# MIDI_CV_atmega_max528_v2_5.net
KiCad netlist of a schematic drawn in EAGLE
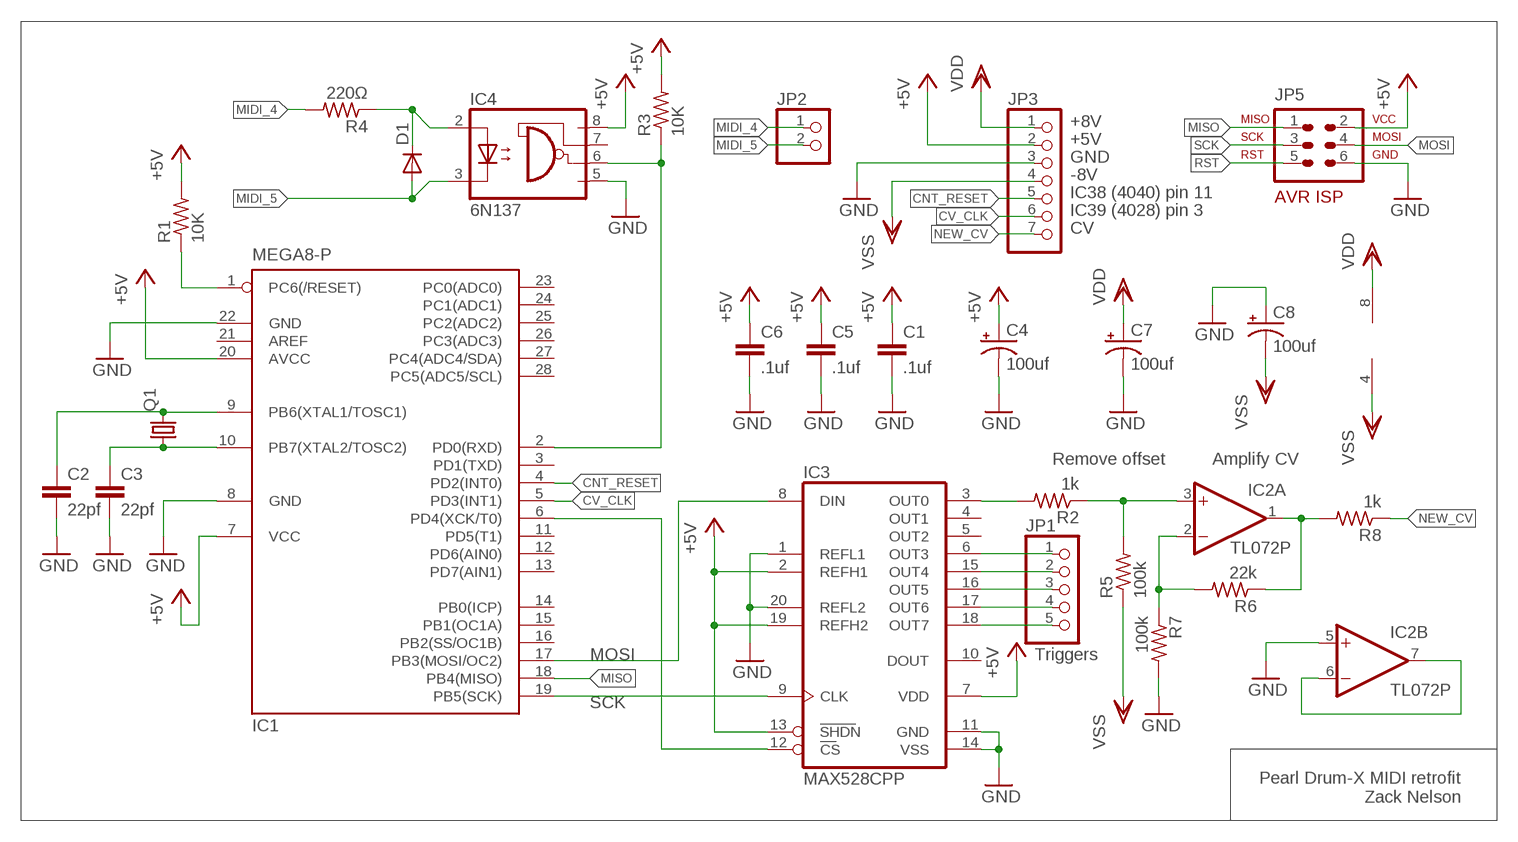
[diagram p0: schematic, sheet 1]

(export (version "E")
  (design (tool "Eeschema 10.0.6"))
  (components
    (comp (ref "C1")
      (value ".1uf")
      (footprint "eagle-import:C025-024X044")
      (libsource (lib "eagle-import") (part "C-EU025-024X044"))
    )
    (comp (ref "C2")
      (value "22pf")
      (footprint "eagle-import:C025-024X044")
      (libsource (lib "eagle-import") (part "C-EU025-024X044"))
    )
    (comp (ref "C3")
      (value "22pf")
      (footprint "eagle-import:C025-024X044")
      (libsource (lib "eagle-import") (part "C-EU025-024X044"))
    )
    (comp (ref "C4")
      (value "100uf")
      (footprint "eagle-import:E1,8-4")
      (libsource (lib "eagle-import") (part "CPOL-USE1.8-4"))
    )
    (comp (ref "C5")
      (value ".1uf")
      (footprint "eagle-import:C025-024X044")
      (libsource (lib "eagle-import") (part "C-EU025-024X044"))
    )
    (comp (ref "C6")
      (value ".1uf")
      (footprint "eagle-import:C025-024X044")
      (libsource (lib "eagle-import") (part "C-EU025-024X044"))
    )
    (comp (ref "C7")
      (value "100uf")
      (footprint "eagle-import:E1,8-4")
      (libsource (lib "eagle-import") (part "CPOL-USE1.8-4"))
    )
    (comp (ref "C8")
      (value "100uf")
      (footprint "eagle-import:E1,8-4")
      (libsource (lib "eagle-import") (part "CPOL-USE1.8-4"))
    )
    (comp (ref "D1")
      (value "DIODE-D-2.5")
      (footprint "eagle-import:D-2.5")
      (libsource (lib "eagle-import") (part "DIODE-D-2.5"))
    )
    (comp (ref "IC1")
      (value "MEGA8-P")
      (footprint "eagle-import:DIL28-3")
      (libsource (lib "eagle-import") (part "MEGA8-P"))
    )
    (comp (ref "IC2")
      (value "TL072P")
      (footprint "eagle-import:DIL08")
      (libsource (lib "eagle-import") (part "TL072P"))
    )
    (comp (ref "IC3")
      (value "MAX528CPP")
      (footprint "eagle-import:DIL20")
      (libsource (lib "eagle-import") (part "MAX528CPP"))
    )
    (comp (ref "IC4")
      (value "6N137")
      (footprint "eagle-import:DIL08")
      (libsource (lib "eagle-import") (part "6N137"))
    )
    (comp (ref "JP1")
      (value "PINHD-1X5")
      (footprint "eagle-import:1X05")
      (libsource (lib "eagle-import") (part "PINHD-1X5"))
    )
    (comp (ref "JP2")
      (value "PINHD-1X2")
      (footprint "eagle-import:1X02")
      (libsource (lib "eagle-import") (part "PINHD-1X2"))
    )
    (comp (ref "JP3")
      (value "PINHD-1X7")
      (footprint "eagle-import:1X07")
      (libsource (lib "eagle-import") (part "PINHD-1X7"))
    )
    (comp (ref "JP5")
      (value "AVR-ISP-6VERT")
      (footprint "eagle-import:AVR-ISP-6")
      (libsource (lib "eagle-import") (part "AVR-ISP-6VERT"))
    )
    (comp (ref "Q1")
      (value "CRYSTALHC18U-V")
      (footprint "eagle-import:HC18U-V")
      (libsource (lib "eagle-import") (part "CRYSTALHC18U-V"))
    )
    (comp (ref "R1")
      (value "10K")
      (footprint "eagle-import:0204V")
      (libsource (lib "eagle-import") (part "R-US_0204/2V"))
    )
    (comp (ref "R2")
      (value "1k")
      (footprint "eagle-import:0204V")
      (libsource (lib "eagle-import") (part "R-US_0204/2V"))
    )
    (comp (ref "R3")
      (value "10K")
      (footprint "eagle-import:0204V")
      (libsource (lib "eagle-import") (part "R-US_0204/2V"))
    )
    (comp (ref "R4")
      (value "220Ω")
      (footprint "eagle-import:0204V")
      (libsource (lib "eagle-import") (part "R-US_0204/2V"))
    )
    (comp (ref "R5")
      (value "100k")
      (footprint "eagle-import:0204V")
      (libsource (lib "eagle-import") (part "R-US_0204/2V"))
    )
    (comp (ref "R6")
      (value "22k")
      (footprint "eagle-import:0204V")
      (libsource (lib "eagle-import") (part "R-US_0204/2V"))
    )
    (comp (ref "R7")
      (value "100k")
      (footprint "eagle-import:0204V")
      (libsource (lib "eagle-import") (part "R-US_0204/2V"))
    )
    (comp (ref "R8")
      (value "1k")
      (footprint "eagle-import:0204V")
      (libsource (lib "eagle-import") (part "R-US_0204/2V"))
    )
  )
  (nets
    (net (code "1") (name "+5V") (class "Default")
      (node (ref "C1") (pin "1") (pinfunction "1_1") (pintype "passive"))
      (node (ref "C4") (pin "+") (pinfunction "+_+") (pintype "passive"))
      (node (ref "C5") (pin "1") (pinfunction "1_1") (pintype "passive"))
      (node (ref "C6") (pin "1") (pinfunction "1_1") (pintype "passive"))
      (node (ref "IC1") (pin "20") (pinfunction "AVCC_20") (pintype "power_in"))
      (node (ref "IC1") (pin "7") (pinfunction "VCC_7") (pintype "power_in"))
      (node (ref "IC3") (pin "13") (pinfunction "SHDN_13") (pintype "input"))
      (node (ref "IC3") (pin "19") (pinfunction "REFH2_19") (pintype "input"))
      (node (ref "IC3") (pin "2") (pinfunction "REFH1_2") (pintype "input"))
      (node (ref "IC3") (pin "7") (pinfunction "VDD_7") (pintype "power_in"))
      (node (ref "IC4") (pin "8") (pinfunction "VCC_8") (pintype "passive"))
      (node (ref "JP3") (pin "2") (pinfunction "2_2") (pintype "passive"))
      (node (ref "JP5") (pin "2") (pinfunction "2_2") (pintype "passive"))
      (node (ref "R1") (pin "2") (pinfunction "2_2") (pintype "passive"))
      (node (ref "R3") (pin "2") (pinfunction "2_2") (pintype "passive"))
    )
    (net (code "2") (name "CNT_RESET") (class "Default")
      (node (ref "IC1") (pin "4") (pinfunction "PD2(INT0)_4") (pintype "bidirectional"))
      (node (ref "JP3") (pin "5") (pinfunction "5_5") (pintype "passive"))
    )
    (net (code "3") (name "CV_CLK") (class "Default")
      (node (ref "IC1") (pin "5") (pinfunction "PD3(INT1)_5") (pintype "bidirectional"))
      (node (ref "JP3") (pin "6") (pinfunction "6_6") (pintype "passive"))
    )
    (net (code "4") (name "GND") (class "Default")
      (node (ref "C1") (pin "2") (pinfunction "2_2") (pintype "passive"))
      (node (ref "C2") (pin "2") (pinfunction "2_2") (pintype "passive"))
      (node (ref "C3") (pin "2") (pinfunction "2_2") (pintype "passive"))
      (node (ref "C4") (pin "-") (pinfunction "-_-") (pintype "passive"))
      (node (ref "C5") (pin "2") (pinfunction "2_2") (pintype "passive"))
      (node (ref "C6") (pin "2") (pinfunction "2_2") (pintype "passive"))
      (node (ref "C7") (pin "-") (pinfunction "-_-") (pintype "passive"))
      (node (ref "C8") (pin "+") (pinfunction "+_+") (pintype "passive"))
      (node (ref "IC1") (pin "22") (pinfunction "GND_22") (pintype "power_in"))
      (node (ref "IC1") (pin "8") (pinfunction "GND_8") (pintype "power_in"))
      (node (ref "IC2") (pin "5") (pinfunction "+IN_5") (pintype "input"))
      (node (ref "IC3") (pin "1") (pinfunction "REFL1_1") (pintype "input"))
      (node (ref "IC3") (pin "11") (pinfunction "GND_11") (pintype "power_in"))
      (node (ref "IC3") (pin "14") (pinfunction "VSS_14") (pintype "power_in"))
      (node (ref "IC3") (pin "20") (pinfunction "REFL2_20") (pintype "input"))
      (node (ref "IC4") (pin "5") (pinfunction "GND_5") (pintype "passive"))
      (node (ref "JP3") (pin "3") (pinfunction "3_3") (pintype "passive"))
      (node (ref "JP5") (pin "6") (pinfunction "6_6") (pintype "passive"))
      (node (ref "R7") (pin "2") (pinfunction "2_2") (pintype "passive"))
    )
    (net (code "5") (name "MIDI_4") (class "Default")
      (node (ref "JP2") (pin "1") (pinfunction "1_1") (pintype "passive"))
      (node (ref "R4") (pin "2") (pinfunction "2_2") (pintype "passive"))
    )
    (net (code "6") (name "MIDI_5") (class "Default")
      (node (ref "D1") (pin "A") (pinfunction "A_A") (pintype "passive"))
      (node (ref "IC4") (pin "3") (pinfunction "C_3") (pintype "passive"))
      (node (ref "JP2") (pin "2") (pinfunction "2_2") (pintype "passive"))
    )
    (net (code "7") (name "MISO") (class "Default")
      (node (ref "IC1") (pin "18") (pinfunction "PB4(MISO)_18") (pintype "bidirectional"))
      (node (ref "JP5") (pin "1") (pinfunction "1_1") (pintype "passive"))
    )
    (net (code "8") (name "MOSI") (class "Default")
      (node (ref "IC1") (pin "17") (pinfunction "PB3(MOSI/OC2)_17") (pintype "bidirectional"))
      (node (ref "IC3") (pin "8") (pinfunction "DIN_8") (pintype "input"))
      (node (ref "JP5") (pin "4") (pinfunction "4_4") (pintype "passive"))
    )
    (net (code "9") (name "NEW_CV") (class "Default")
      (node (ref "JP3") (pin "7") (pinfunction "7_7") (pintype "passive"))
      (node (ref "R8") (pin "1") (pinfunction "1_1") (pintype "passive"))
    )
    (net (code "10") (name "Net-(IC1-PB6(XTAL1{slash}TOSC1))") (class "Default")
      (node (ref "C2") (pin "1") (pinfunction "1_1") (pintype "passive"))
      (node (ref "IC1") (pin "9") (pinfunction "PB6(XTAL1/TOSC1)_9") (pintype "bidirectional"))
      (node (ref "Q1") (pin "2") (pinfunction "2_2") (pintype "passive"))
    )
    (net (code "11") (name "Net-(IC1-PB7(XTAL2{slash}TOSC2))") (class "Default")
      (node (ref "C3") (pin "1") (pinfunction "1_1") (pintype "passive"))
      (node (ref "IC1") (pin "10") (pinfunction "PB7(XTAL2/TOSC2)_10") (pintype "bidirectional"))
      (node (ref "Q1") (pin "1") (pinfunction "1_1") (pintype "passive"))
    )
    (net (code "12") (name "Net-(IC1-PD0(RXD))") (class "Default")
      (node (ref "IC1") (pin "2") (pinfunction "PD0(RXD)_2") (pintype "bidirectional"))
      (node (ref "IC4") (pin "6") (pinfunction "VO_6") (pintype "passive"))
      (node (ref "R3") (pin "1") (pinfunction "1_1") (pintype "passive"))
    )
    (net (code "13") (name "Net-(IC1-PD4(XCK{slash}T0))") (class "Default")
      (node (ref "IC1") (pin "6") (pinfunction "PD4(XCK/T0)_6") (pintype "bidirectional"))
      (node (ref "IC3") (pin "12") (pinfunction "CS_12") (pintype "input"))
    )
    (net (code "14") (name "Net-(IC2A-+IN)") (class "Default")
      (node (ref "IC2") (pin "3") (pinfunction "+IN_3") (pintype "input"))
      (node (ref "R2") (pin "1") (pinfunction "1_1") (pintype "passive"))
      (node (ref "R5") (pin "2") (pinfunction "2_2") (pintype "passive"))
    )
    (net (code "15") (name "Net-(IC2A--IN)") (class "Default")
      (node (ref "IC2") (pin "2") (pinfunction "-IN_2") (pintype "input"))
      (node (ref "R6") (pin "2") (pinfunction "2_2") (pintype "passive"))
      (node (ref "R7") (pin "1") (pinfunction "1_1") (pintype "passive"))
    )
    (net (code "16") (name "Net-(IC2A-OUT)") (class "Default")
      (node (ref "IC2") (pin "1") (pinfunction "OUT_1") (pintype "output"))
      (node (ref "R6") (pin "1") (pinfunction "1_1") (pintype "passive"))
      (node (ref "R8") (pin "2") (pinfunction "2_2") (pintype "passive"))
    )
    (net (code "17") (name "Net-(IC2B--IN)") (class "Default")
      (node (ref "IC2") (pin "6") (pinfunction "-IN_6") (pintype "input"))
      (node (ref "IC2") (pin "7") (pinfunction "OUT_7") (pintype "output"))
    )
    (net (code "18") (name "Net-(IC3-OUT0)") (class "Default")
      (node (ref "IC3") (pin "3") (pinfunction "OUT0_3") (pintype "output"))
      (node (ref "R2") (pin "2") (pinfunction "2_2") (pintype "passive"))
    )
    (net (code "19") (name "Net-(IC3-OUT3)") (class "Default")
      (node (ref "IC3") (pin "6") (pinfunction "OUT3_6") (pintype "output"))
      (node (ref "JP1") (pin "1") (pinfunction "1_1") (pintype "passive"))
    )
    (net (code "20") (name "Net-(IC3-OUT4)") (class "Default")
      (node (ref "IC3") (pin "15") (pinfunction "OUT4_15") (pintype "output"))
      (node (ref "JP1") (pin "2") (pinfunction "2_2") (pintype "passive"))
    )
    (net (code "21") (name "Net-(IC3-OUT5)") (class "Default")
      (node (ref "IC3") (pin "16") (pinfunction "OUT5_16") (pintype "output"))
      (node (ref "JP1") (pin "3") (pinfunction "3_3") (pintype "passive"))
    )
    (net (code "22") (name "Net-(IC3-OUT6)") (class "Default")
      (node (ref "IC3") (pin "17") (pinfunction "OUT6_17") (pintype "output"))
      (node (ref "JP1") (pin "4") (pinfunction "4_4") (pintype "passive"))
    )
    (net (code "23") (name "Net-(IC3-OUT7)") (class "Default")
      (node (ref "IC3") (pin "18") (pinfunction "OUT7_18") (pintype "output"))
      (node (ref "JP1") (pin "5") (pinfunction "5_5") (pintype "passive"))
    )
    (net (code "24") (name "Net-(IC4-A)") (class "Default")
      (node (ref "D1") (pin "C") (pinfunction "C_C") (pintype "passive"))
      (node (ref "IC4") (pin "2") (pinfunction "A_2") (pintype "passive"))
      (node (ref "R4") (pin "1") (pinfunction "1_1") (pintype "passive"))
    )
    (net (code "25") (name "RST") (class "Default")
      (node (ref "IC1") (pin "1") (pinfunction "PC6(/RESET)_1") (pintype "bidirectional"))
      (node (ref "JP5") (pin "5") (pinfunction "5_5") (pintype "passive"))
      (node (ref "R1") (pin "1") (pinfunction "1_1") (pintype "passive"))
    )
    (net (code "26") (name "SCK") (class "Default")
      (node (ref "IC1") (pin "19") (pinfunction "PB5(SCK)_19") (pintype "bidirectional"))
      (node (ref "IC3") (pin "9") (pinfunction "CLK_9") (pintype "input"))
      (node (ref "JP5") (pin "3") (pinfunction "3_3") (pintype "passive"))
    )
    (net (code "27") (name "VDD") (class "Default")
      (node (ref "C7") (pin "+") (pinfunction "+_+") (pintype "passive"))
      (node (ref "IC2") (pin "8") (pinfunction "V+_8") (pintype "power_in"))
      (node (ref "JP3") (pin "1") (pinfunction "1_1") (pintype "passive"))
    )
    (net (code "28") (name "VSS") (class "Default")
      (node (ref "C8") (pin "-") (pinfunction "-_-") (pintype "passive"))
      (node (ref "IC2") (pin "4") (pinfunction "V-_4") (pintype "power_in"))
      (node (ref "JP3") (pin "4") (pinfunction "4_4") (pintype "passive"))
      (node (ref "R5") (pin "1") (pinfunction "1_1") (pintype "passive"))
    )
    (net (code "29") (name "unconnected-(IC1-AREF-Pad21)") (class "Default")
      (node (ref "IC1") (pin "21") (pinfunction "AREF_21") (pintype "passive"))
    )
    (net (code "30") (name "unconnected-(IC1-PB0(ICP)-Pad14)") (class "Default")
      (node (ref "IC1") (pin "14") (pinfunction "PB0(ICP)_14") (pintype "bidirectional"))
    )
    (net (code "31") (name "unconnected-(IC1-PB1(OC1A)-Pad15)") (class "Default")
      (node (ref "IC1") (pin "15") (pinfunction "PB1(OC1A)_15") (pintype "bidirectional"))
    )
    (net (code "32") (name "unconnected-(IC1-PB2(SS{slash}OC1B)-Pad16)") (class "Default")
      (node (ref "IC1") (pin "16") (pinfunction "PB2(SS/OC1B)_16") (pintype "bidirectional"))
    )
    (net (code "33") (name "unconnected-(IC1-PC0(ADC0)-Pad23)") (class "Default")
      (node (ref "IC1") (pin "23") (pinfunction "PC0(ADC0)_23") (pintype "bidirectional"))
    )
    (net (code "34") (name "unconnected-(IC1-PC1(ADC1)-Pad24)") (class "Default")
      (node (ref "IC1") (pin "24") (pinfunction "PC1(ADC1)_24") (pintype "bidirectional"))
    )
    (net (code "35") (name "unconnected-(IC1-PC2(ADC2)-Pad25)") (class "Default")
      (node (ref "IC1") (pin "25") (pinfunction "PC2(ADC2)_25") (pintype "bidirectional"))
    )
    (net (code "36") (name "unconnected-(IC1-PC3(ADC3)-Pad26)") (class "Default")
      (node (ref "IC1") (pin "26") (pinfunction "PC3(ADC3)_26") (pintype "bidirectional"))
    )
    (net (code "37") (name "unconnected-(IC1-PC4(ADC4{slash}SDA)-Pad27)") (class "Default")
      (node (ref "IC1") (pin "27") (pinfunction "PC4(ADC4/SDA)_27") (pintype "bidirectional"))
    )
    (net (code "38") (name "unconnected-(IC1-PC5(ADC5{slash}SCL)-Pad28)") (class "Default")
      (node (ref "IC1") (pin "28") (pinfunction "PC5(ADC5/SCL)_28") (pintype "bidirectional"))
    )
    (net (code "39") (name "unconnected-(IC1-PD1(TXD)-Pad3)") (class "Default")
      (node (ref "IC1") (pin "3") (pinfunction "PD1(TXD)_3") (pintype "bidirectional"))
    )
    (net (code "40") (name "unconnected-(IC1-PD5(T1)-Pad11)") (class "Default")
      (node (ref "IC1") (pin "11") (pinfunction "PD5(T1)_11") (pintype "bidirectional"))
    )
    (net (code "41") (name "unconnected-(IC1-PD6(AIN0)-Pad12)") (class "Default")
      (node (ref "IC1") (pin "12") (pinfunction "PD6(AIN0)_12") (pintype "bidirectional"))
    )
    (net (code "42") (name "unconnected-(IC1-PD7(AIN1)-Pad13)") (class "Default")
      (node (ref "IC1") (pin "13") (pinfunction "PD7(AIN1)_13") (pintype "bidirectional"))
    )
    (net (code "43") (name "unconnected-(IC3-DOUT-Pad10)") (class "Default")
      (node (ref "IC3") (pin "10") (pinfunction "DOUT_10") (pintype "output"))
    )
    (net (code "44") (name "unconnected-(IC3-OUT1-Pad4)") (class "Default")
      (node (ref "IC3") (pin "4") (pinfunction "OUT1_4") (pintype "output"))
    )
    (net (code "45") (name "unconnected-(IC3-OUT2-Pad5)") (class "Default")
      (node (ref "IC3") (pin "5") (pinfunction "OUT2_5") (pintype "output"))
    )
    (net (code "46") (name "unconnected-(IC4-VE-Pad7)") (class "Default")
      (node (ref "IC4") (pin "7") (pinfunction "VE_7") (pintype "passive"))
    )
  )
)
